# Ismailabi2.net
KiCad netlist of a schematic drawn in EAGLE
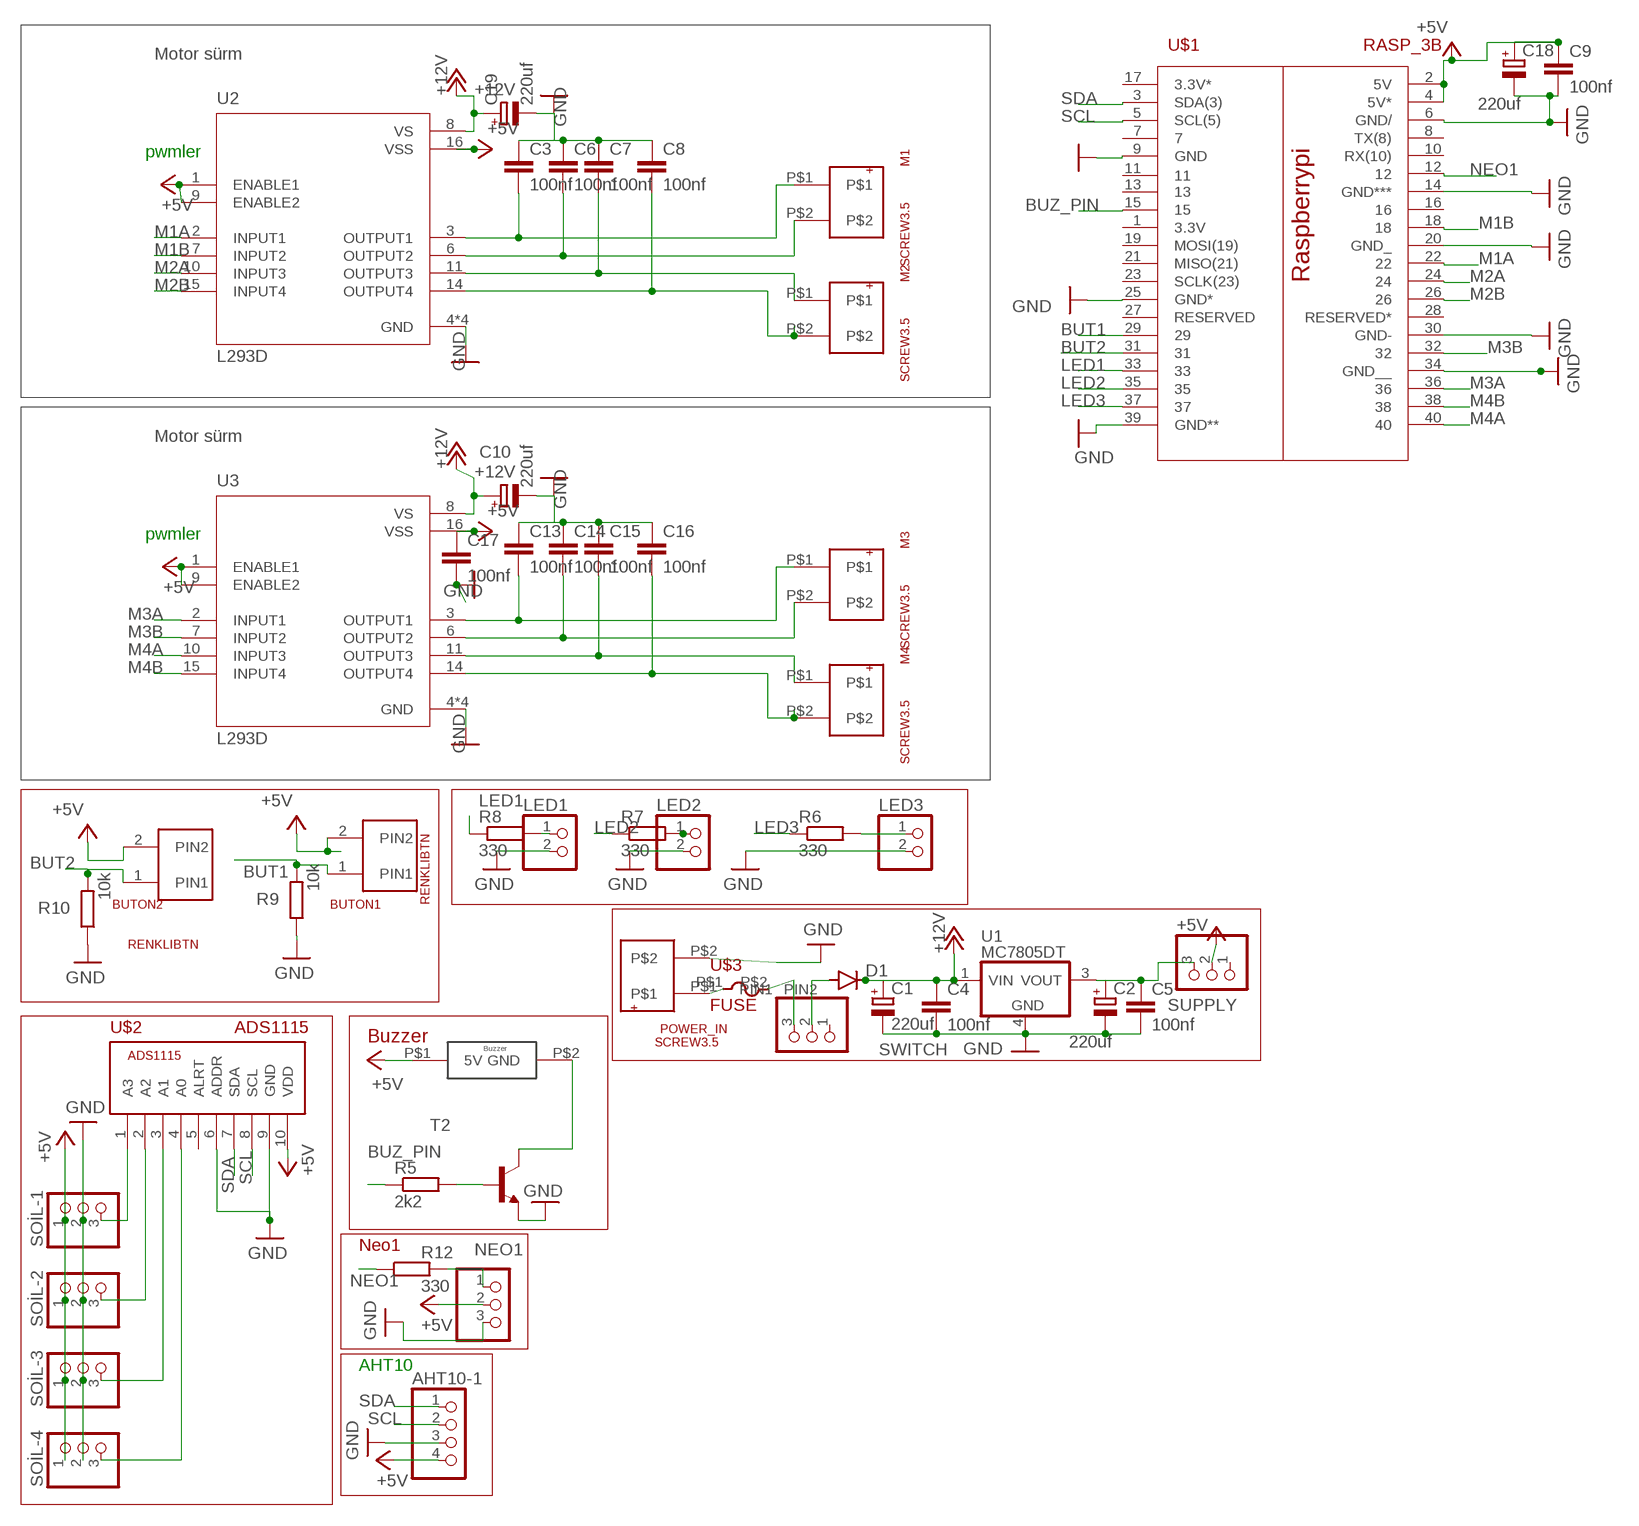
[diagram p0: schematic, sheet 1]

(export (version "E")
  (design (tool "Eeschema 10.0.6"))
  (components
    (comp (ref "AHT10-1")
      (value "PINHD-1X4")
      (footprint "eagle-import:1X04")
      (libsource (lib "eagle-import") (part "PINHD-1X4"))
    )
    (comp (ref "BUTON1")
      (value "RENKLIBTN")
      (footprint "eagle-import:BTN")
      (libsource (lib "eagle-import") (part "RENKLIBTN"))
    )
    (comp (ref "BUTON2")
      (value "RENKLIBTN")
      (footprint "eagle-import:BTN")
      (libsource (lib "eagle-import") (part "RENKLIBTN"))
    )
    (comp (ref "C1")
      (value "220uf")
      (footprint "eagle-import:153CLV-0605")
      (libsource (lib "eagle-import") (part "CPOL-EU153CLV-0605"))
    )
    (comp (ref "C2")
      (value "220uf")
      (footprint "eagle-import:153CLV-0605")
      (libsource (lib "eagle-import") (part "CPOL-EU153CLV-0605"))
    )
    (comp (ref "C3")
      (value "100nf")
      (footprint "eagle-import:C0603")
      (libsource (lib "eagle-import") (part "C-EUC0603"))
    )
    (comp (ref "C4")
      (value "100nf")
      (footprint "eagle-import:C0603")
      (libsource (lib "eagle-import") (part "C-EUC0603"))
    )
    (comp (ref "C5")
      (value "100nf")
      (footprint "eagle-import:C0603")
      (libsource (lib "eagle-import") (part "C-EUC0603"))
    )
    (comp (ref "C6")
      (value "100nf")
      (footprint "eagle-import:C0603")
      (libsource (lib "eagle-import") (part "C-EUC0603"))
    )
    (comp (ref "C7")
      (value "100nf")
      (footprint "eagle-import:C0603")
      (libsource (lib "eagle-import") (part "C-EUC0603"))
    )
    (comp (ref "C8")
      (value "100nf")
      (footprint "eagle-import:C0603")
      (libsource (lib "eagle-import") (part "C-EUC0603"))
    )
    (comp (ref "C9")
      (value "100nf")
      (footprint "eagle-import:C0603")
      (libsource (lib "eagle-import") (part "C-EUC0603"))
    )
    (comp (ref "C10")
      (value "220uf")
      (footprint "eagle-import:153CLV-0605")
      (libsource (lib "eagle-import") (part "CPOL-EU153CLV-0605"))
    )
    (comp (ref "C13")
      (value "100nf")
      (footprint "eagle-import:C0603")
      (libsource (lib "eagle-import") (part "C-EUC0603"))
    )
    (comp (ref "C14")
      (value "100nf")
      (footprint "eagle-import:C0603")
      (libsource (lib "eagle-import") (part "C-EUC0603"))
    )
    (comp (ref "C15")
      (value "100nf")
      (footprint "eagle-import:C0603")
      (libsource (lib "eagle-import") (part "C-EUC0603"))
    )
    (comp (ref "C16")
      (value "100nf")
      (footprint "eagle-import:C0603")
      (libsource (lib "eagle-import") (part "C-EUC0603"))
    )
    (comp (ref "C17")
      (value "100nf")
      (footprint "eagle-import:C0603")
      (libsource (lib "eagle-import") (part "C-EUC0603"))
    )
    (comp (ref "C18")
      (value "220uf")
      (footprint "eagle-import:153CLV-0605")
      (libsource (lib "eagle-import") (part "CPOL-EU153CLV-0605"))
    )
    (comp (ref "C19")
      (value "220uf")
      (footprint "eagle-import:153CLV-0605")
      (libsource (lib "eagle-import") (part "CPOL-EU153CLV-0605"))
    )
    (comp (ref "D1")
      (value "DIODE-DO-214AC")
      (footprint "eagle-import:DO-214AC")
      (libsource (lib "eagle-import") (part "DIODE-DO-214AC"))
    )
    (comp (ref "LED1")
      (value "PINHD-1X2")
      (footprint "eagle-import:1X02")
      (libsource (lib "eagle-import") (part "PINHD-1X2"))
    )
    (comp (ref "LED2")
      (value "PINHD-1X2")
      (footprint "eagle-import:1X02")
      (libsource (lib "eagle-import") (part "PINHD-1X2"))
    )
    (comp (ref "LED3")
      (value "PINHD-1X2")
      (footprint "eagle-import:1X02")
      (libsource (lib "eagle-import") (part "PINHD-1X2"))
    )
    (comp (ref "M1")
      (value "SCREW3.5")
      (footprint "eagle-import:CREWT")
      (libsource (lib "eagle-import") (part "SCREW3.5"))
    )
    (comp (ref "M2")
      (value "SCREW3.5")
      (footprint "eagle-import:CREWT")
      (libsource (lib "eagle-import") (part "SCREW3.5"))
    )
    (comp (ref "M3")
      (value "SCREW3.5")
      (footprint "eagle-import:CREWT")
      (libsource (lib "eagle-import") (part "SCREW3.5"))
    )
    (comp (ref "M4")
      (value "SCREW3.5")
      (footprint "eagle-import:CREWT")
      (libsource (lib "eagle-import") (part "SCREW3.5"))
    )
    (comp (ref "NEO1")
      (value "PINHD-1X3")
      (footprint "eagle-import:1X03")
      (libsource (lib "eagle-import") (part "PINHD-1X3"))
    )
    (comp (ref "POWER_IN")
      (value "SCREW3.5")
      (footprint "eagle-import:CREWT")
      (libsource (lib "eagle-import") (part "SCREW3.5"))
    )
    (comp (ref "R5")
      (value "2k2")
      (footprint "eagle-import:R0805")
      (libsource (lib "eagle-import") (part "R-EU_R0805"))
    )
    (comp (ref "R6")
      (value "330")
      (footprint "eagle-import:R0805")
      (libsource (lib "eagle-import") (part "R-EU_R0805"))
    )
    (comp (ref "R7")
      (value "330")
      (footprint "eagle-import:R0805")
      (libsource (lib "eagle-import") (part "R-EU_R0805"))
    )
    (comp (ref "R8")
      (value "330")
      (footprint "eagle-import:R0805")
      (libsource (lib "eagle-import") (part "R-EU_R0805"))
    )
    (comp (ref "R9")
      (value "10k")
      (footprint "eagle-import:R0805")
      (libsource (lib "eagle-import") (part "R-EU_R0805"))
    )
    (comp (ref "R10")
      (value "10k")
      (footprint "eagle-import:R0805")
      (libsource (lib "eagle-import") (part "R-EU_R0805"))
    )
    (comp (ref "R12")
      (value "330")
      (footprint "eagle-import:R0805")
      (libsource (lib "eagle-import") (part "R-EU_R0805"))
    )
    (comp (ref "SOİL-1")
      (value "PINHD-1X3")
      (footprint "eagle-import:1X03")
      (libsource (lib "eagle-import") (part "PINHD-1X3"))
    )
    (comp (ref "SOİL-2")
      (value "PINHD-1X3")
      (footprint "eagle-import:1X03")
      (libsource (lib "eagle-import") (part "PINHD-1X3"))
    )
    (comp (ref "SOİL-3")
      (value "PINHD-1X3")
      (footprint "eagle-import:1X03")
      (libsource (lib "eagle-import") (part "PINHD-1X3"))
    )
    (comp (ref "SOİL-4")
      (value "PINHD-1X3")
      (footprint "eagle-import:1X03")
      (libsource (lib "eagle-import") (part "PINHD-1X3"))
    )
    (comp (ref "SUPPLY")
      (value "PINHD-1X3")
      (footprint "eagle-import:1X03")
      (libsource (lib "eagle-import") (part "PINHD-1X3"))
    )
    (comp (ref "SWITCH")
      (value "PINHD-1X3")
      (footprint "eagle-import:1X03")
      (libsource (lib "eagle-import") (part "PINHD-1X3"))
    )
    (comp (ref "T2")
      (value "2N2222-NPN-TO92-EBC")
      (footprint "eagle-import:TO92-EBC")
      (libsource (lib "eagle-import") (part "-NPN-TO92-EBC2N2222"))
    )
    (comp (ref "U$1")
      (value "RASP_3B")
      (footprint "eagle-import:PI3B+")
      (libsource (lib "eagle-import") (part "RASP_3B"))
    )
    (comp (ref "U$2")
      (value "ADS1115")
      (footprint "eagle-import:ADS1115")
      (libsource (lib "eagle-import") (part "ADS1115"))
    )
    (comp (ref "U$3")
      (value "FUSE")
      (footprint "eagle-import:FUSE")
      (libsource (lib "eagle-import") (part "FUSE"))
    )
    (comp (ref "U$4")
      (value "BUZZER")
      (footprint "eagle-import:BUZZER")
      (libsource (lib "eagle-import") (part "BUZZER"))
    )
    (comp (ref "U1")
      (value "MC7805DT")
      (footprint "eagle-import:DPAK-3")
      (libsource (lib "eagle-import") (part "MC78DT05"))
    )
    (comp (ref "U2")
      (value "L293D")
      (footprint "eagle-import:DIP880W50P254L2000H510Q16")
      (fields (field (name "MF") "STMicroelectronics"))
      (libsource (lib "eagle-import") (part "L293D"))
    )
    (comp (ref "U3")
      (value "L293D")
      (footprint "eagle-import:DIP880W50P254L2000H510Q16")
      (fields (field (name "MF") "STMicroelectronics"))
      (libsource (lib "eagle-import") (part "L293D"))
    )
  )
  (nets
    (net (code "1") (name "+5V") (class "Default")
      (node (ref "AHT10-1") (pin "4") (pinfunction "4_4") (pintype "passive"))
      (node (ref "BUTON1") (pin "2") (pinfunction "PIN2_2") (pintype "bidirectional"))
      (node (ref "BUTON2") (pin "2") (pinfunction "PIN2_2") (pintype "bidirectional"))
      (node (ref "C17") (pin "1") (pinfunction "1_1") (pintype "passive"))
      (node (ref "C18") (pin "+") (pinfunction "+_+") (pintype "passive"))
      (node (ref "C9") (pin "1") (pinfunction "1_1") (pintype "passive"))
      (node (ref "NEO1") (pin "2") (pinfunction "2_2") (pintype "passive"))
      (node (ref "SOİL-1") (pin "1") (pinfunction "1_1") (pintype "passive"))
      (node (ref "SOİL-2") (pin "1") (pinfunction "1_1") (pintype "passive"))
      (node (ref "SOİL-3") (pin "1") (pinfunction "1_1") (pintype "passive"))
      (node (ref "SOİL-4") (pin "1") (pinfunction "1_1") (pintype "passive"))
      (node (ref "SUPPLY") (pin "2") (pinfunction "2_2") (pintype "passive"))
      (node (ref "U$1") (pin "2") (pinfunction "5V_2") (pintype "bidirectional"))
      (node (ref "U$1") (pin "4") (pinfunction "5V*_4") (pintype "bidirectional"))
      (node (ref "U$2") (pin "10") (pinfunction "VDD_10") (pintype "bidirectional"))
      (node (ref "U$4") (pin "P$1") (pinfunction "5V_P$1") (pintype "bidirectional"))
      (node (ref "U2") (pin "1") (pinfunction "ENABLE1_1") (pintype "input"))
      (node (ref "U2") (pin "16") (pinfunction "VSS_16") (pintype "power_in"))
      (node (ref "U2") (pin "9") (pinfunction "ENABLE2_9") (pintype "input"))
      (node (ref "U3") (pin "1") (pinfunction "ENABLE1_1") (pintype "input"))
      (node (ref "U3") (pin "16") (pinfunction "VSS_16") (pintype "power_in"))
      (node (ref "U3") (pin "9") (pinfunction "ENABLE2_9") (pintype "input"))
    )
    (net (code "2") (name "+12V") (class "Default")
      (node (ref "C1") (pin "+") (pinfunction "+_+") (pintype "passive"))
      (node (ref "C10") (pin "+") (pinfunction "+_+") (pintype "passive"))
      (node (ref "C19") (pin "+") (pinfunction "+_+") (pintype "passive"))
      (node (ref "C4") (pin "1") (pinfunction "1_1") (pintype "passive"))
      (node (ref "D1") (pin "C") (pinfunction "C_C") (pintype "passive"))
      (node (ref "U1") (pin "1") (pinfunction "VIN_1") (pintype "power_in"))
      (node (ref "U2") (pin "8") (pinfunction "VS_8") (pintype "power_in"))
      (node (ref "U3") (pin "8") (pinfunction "VS_8") (pintype "power_in"))
    )
    (net (code "3") (name "/BUT1") (class "Default")
      (node (ref "BUTON1") (pin "1") (pinfunction "PIN1_1") (pintype "bidirectional"))
      (node (ref "R9") (pin "2") (pinfunction "2_2") (pintype "passive"))
      (node (ref "U$1") (pin "29") (pinfunction "29_29") (pintype "bidirectional"))
    )
    (net (code "4") (name "/BUT2") (class "Default")
      (node (ref "BUTON2") (pin "1") (pinfunction "PIN1_1") (pintype "bidirectional"))
      (node (ref "R10") (pin "2") (pinfunction "2_2") (pintype "passive"))
      (node (ref "U$1") (pin "31") (pinfunction "31_31") (pintype "bidirectional"))
    )
    (net (code "5") (name "/BUZ_PIN") (class "Default")
      (node (ref "R5") (pin "1") (pinfunction "1_1") (pintype "passive"))
      (node (ref "U$1") (pin "15") (pinfunction "15_15") (pintype "bidirectional"))
    )
    (net (code "6") (name "/LED1") (class "Default")
      (node (ref "R8") (pin "1") (pinfunction "1_1") (pintype "passive"))
      (node (ref "U$1") (pin "33") (pinfunction "33_33") (pintype "bidirectional"))
    )
    (net (code "7") (name "/LED2") (class "Default")
      (node (ref "R7") (pin "1") (pinfunction "1_1") (pintype "passive"))
      (node (ref "U$1") (pin "35") (pinfunction "35_35") (pintype "bidirectional"))
    )
    (net (code "8") (name "/LED3") (class "Default")
      (node (ref "R6") (pin "1") (pinfunction "1_1") (pintype "passive"))
      (node (ref "U$1") (pin "37") (pinfunction "37_37") (pintype "bidirectional"))
    )
    (net (code "9") (name "/M1A") (class "Default")
      (node (ref "U$1") (pin "22") (pinfunction "22_22") (pintype "bidirectional"))
      (node (ref "U2") (pin "2") (pinfunction "INPUT1_2") (pintype "input"))
    )
    (net (code "10") (name "/M1B") (class "Default")
      (node (ref "U$1") (pin "18") (pinfunction "18_18") (pintype "bidirectional"))
      (node (ref "U2") (pin "7") (pinfunction "INPUT2_7") (pintype "input"))
    )
    (net (code "11") (name "/M2A") (class "Default")
      (node (ref "U$1") (pin "24") (pinfunction "24_24") (pintype "bidirectional"))
      (node (ref "U2") (pin "10") (pinfunction "INPUT3_10") (pintype "input"))
    )
    (net (code "12") (name "/M2B") (class "Default")
      (node (ref "U$1") (pin "26") (pinfunction "26_26") (pintype "bidirectional"))
      (node (ref "U2") (pin "15") (pinfunction "INPUT4_15") (pintype "input"))
    )
    (net (code "13") (name "/M3A") (class "Default")
      (node (ref "U$1") (pin "36") (pinfunction "36_36") (pintype "bidirectional"))
      (node (ref "U3") (pin "2") (pinfunction "INPUT1_2") (pintype "input"))
    )
    (net (code "14") (name "/M3B") (class "Default")
      (node (ref "U$1") (pin "32") (pinfunction "32_32") (pintype "bidirectional"))
      (node (ref "U3") (pin "7") (pinfunction "INPUT2_7") (pintype "input"))
    )
    (net (code "15") (name "/M4A") (class "Default")
      (node (ref "U$1") (pin "40") (pinfunction "40_40") (pintype "bidirectional"))
      (node (ref "U3") (pin "10") (pinfunction "INPUT3_10") (pintype "input"))
    )
    (net (code "16") (name "/M4B") (class "Default")
      (node (ref "U$1") (pin "38") (pinfunction "38_38") (pintype "bidirectional"))
      (node (ref "U3") (pin "15") (pinfunction "INPUT4_15") (pintype "input"))
    )
    (net (code "17") (name "/NEO1") (class "Default")
      (node (ref "R12") (pin "1") (pinfunction "1_1") (pintype "passive"))
      (node (ref "U$1") (pin "12") (pinfunction "12_12") (pintype "bidirectional"))
    )
    (net (code "18") (name "/SCL") (class "Default")
      (node (ref "AHT10-1") (pin "2") (pinfunction "2_2") (pintype "passive"))
      (node (ref "U$1") (pin "5") (pinfunction "SCL(5)_5") (pintype "bidirectional"))
      (node (ref "U$2") (pin "8") (pinfunction "SCL_8") (pintype "bidirectional"))
    )
    (net (code "19") (name "/SDA") (class "Default")
      (node (ref "AHT10-1") (pin "1") (pinfunction "1_1") (pintype "passive"))
      (node (ref "U$1") (pin "3") (pinfunction "SDA(3)_3") (pintype "bidirectional"))
      (node (ref "U$2") (pin "7") (pinfunction "SDA_7") (pintype "bidirectional"))
    )
    (net (code "20") (name "GND") (class "Default")
      (node (ref "AHT10-1") (pin "3") (pinfunction "3_3") (pintype "passive"))
      (node (ref "C1") (pin "-") (pinfunction "-_-") (pintype "passive"))
      (node (ref "C10") (pin "-") (pinfunction "-_-") (pintype "passive"))
      (node (ref "C13") (pin "1") (pinfunction "1_1") (pintype "passive"))
      (node (ref "C14") (pin "1") (pinfunction "1_1") (pintype "passive"))
      (node (ref "C15") (pin "1") (pinfunction "1_1") (pintype "passive"))
      (node (ref "C16") (pin "1") (pinfunction "1_1") (pintype "passive"))
      (node (ref "C17") (pin "2") (pinfunction "2_2") (pintype "passive"))
      (node (ref "C18") (pin "-") (pinfunction "-_-") (pintype "passive"))
      (node (ref "C19") (pin "-") (pinfunction "-_-") (pintype "passive"))
      (node (ref "C2") (pin "-") (pinfunction "-_-") (pintype "passive"))
      (node (ref "C3") (pin "1") (pinfunction "1_1") (pintype "passive"))
      (node (ref "C4") (pin "2") (pinfunction "2_2") (pintype "passive"))
      (node (ref "C5") (pin "2") (pinfunction "2_2") (pintype "passive"))
      (node (ref "C6") (pin "1") (pinfunction "1_1") (pintype "passive"))
      (node (ref "C7") (pin "1") (pinfunction "1_1") (pintype "passive"))
      (node (ref "C8") (pin "1") (pinfunction "1_1") (pintype "passive"))
      (node (ref "C9") (pin "2") (pinfunction "2_2") (pintype "passive"))
      (node (ref "LED1") (pin "2") (pinfunction "2_2") (pintype "passive"))
      (node (ref "LED2") (pin "2") (pinfunction "2_2") (pintype "passive"))
      (node (ref "LED3") (pin "2") (pinfunction "2_2") (pintype "passive"))
      (node (ref "NEO1") (pin "3") (pinfunction "3_3") (pintype "passive"))
      (node (ref "POWER_IN") (pin "P$2") (pinfunction "P$2_P$2") (pintype "bidirectional"))
      (node (ref "R10") (pin "1") (pinfunction "1_1") (pintype "passive"))
      (node (ref "R9") (pin "1") (pinfunction "1_1") (pintype "passive"))
      (node (ref "SOİL-1") (pin "2") (pinfunction "2_2") (pintype "passive"))
      (node (ref "SOİL-2") (pin "2") (pinfunction "2_2") (pintype "passive"))
      (node (ref "SOİL-3") (pin "2") (pinfunction "2_2") (pintype "passive"))
      (node (ref "SOİL-4") (pin "2") (pinfunction "2_2") (pintype "passive"))
      (node (ref "T2") (pin "E") (pinfunction "E_E") (pintype "passive"))
      (node (ref "U$1") (pin "14") (pinfunction "GND***_14") (pintype "bidirectional"))
      (node (ref "U$1") (pin "20") (pinfunction "GND__20") (pintype "bidirectional"))
      (node (ref "U$1") (pin "25") (pinfunction "GND*_25") (pintype "bidirectional"))
      (node (ref "U$1") (pin "30") (pinfunction "GND-_30") (pintype "bidirectional"))
      (node (ref "U$1") (pin "34") (pinfunction "GND___34") (pintype "bidirectional"))
      (node (ref "U$1") (pin "39") (pinfunction "GND**_39") (pintype "bidirectional"))
      (node (ref "U$1") (pin "6") (pinfunction "GND/_6") (pintype "bidirectional"))
      (node (ref "U$1") (pin "9") (pinfunction "GND_9") (pintype "bidirectional"))
      (node (ref "U$2") (pin "6") (pinfunction "ADDR_6") (pintype "bidirectional"))
      (node (ref "U$2") (pin "9") (pinfunction "GND_9") (pintype "bidirectional"))
      (node (ref "U1") (pin "4") (pinfunction "GND_4") (pintype "power_in"))
      (node (ref "U2") (pin "12") (pinfunction "GND_12") (pintype "power_in"))
      (node (ref "U2") (pin "13") (pinfunction "GND_13") (pintype "power_in"))
      (node (ref "U2") (pin "4") (pinfunction "GND_4") (pintype "power_in"))
      (node (ref "U2") (pin "5") (pinfunction "GND_5") (pintype "power_in"))
      (node (ref "U3") (pin "12") (pinfunction "GND_12") (pintype "power_in"))
      (node (ref "U3") (pin "13") (pinfunction "GND_13") (pintype "power_in"))
      (node (ref "U3") (pin "4") (pinfunction "GND_4") (pintype "power_in"))
      (node (ref "U3") (pin "5") (pinfunction "GND_5") (pintype "power_in"))
    )
    (net (code "21") (name "Net-(D1-PadA)") (class "Default")
      (node (ref "D1") (pin "A") (pinfunction "A_A") (pintype "passive"))
      (node (ref "SWITCH") (pin "2") (pinfunction "2_2") (pintype "passive"))
    )
    (net (code "22") (name "Net-(LED1-Pad1)") (class "Default")
      (node (ref "LED1") (pin "1") (pinfunction "1_1") (pintype "passive"))
      (node (ref "R8") (pin "2") (pinfunction "2_2") (pintype "passive"))
    )
    (net (code "23") (name "Net-(LED2-Pad1)") (class "Default")
      (node (ref "LED2") (pin "1") (pinfunction "1_1") (pintype "passive"))
      (node (ref "R7") (pin "2") (pinfunction "2_2") (pintype "passive"))
    )
    (net (code "24") (name "Net-(LED3-Pad1)") (class "Default")
      (node (ref "LED3") (pin "1") (pinfunction "1_1") (pintype "passive"))
      (node (ref "R6") (pin "2") (pinfunction "2_2") (pintype "passive"))
    )
    (net (code "25") (name "Net-(NEO1-Pad1)") (class "Default")
      (node (ref "NEO1") (pin "1") (pinfunction "1_1") (pintype "passive"))
      (node (ref "R12") (pin "2") (pinfunction "2_2") (pintype "passive"))
    )
    (net (code "26") (name "Net-(R5-Pad2)") (class "Default")
      (node (ref "R5") (pin "2") (pinfunction "2_2") (pintype "passive"))
      (node (ref "T2") (pin "B") (pinfunction "B_B") (pintype "passive"))
    )
    (net (code "27") (name "Net-(U$2-A0)") (class "Default")
      (node (ref "SOİL-4") (pin "3") (pinfunction "3_3") (pintype "passive"))
      (node (ref "U$2") (pin "4") (pinfunction "A0_4") (pintype "bidirectional"))
    )
    (net (code "28") (name "Net-(U$2-A1)") (class "Default")
      (node (ref "SOİL-3") (pin "3") (pinfunction "3_3") (pintype "passive"))
      (node (ref "U$2") (pin "3") (pinfunction "A1_3") (pintype "bidirectional"))
    )
    (net (code "29") (name "Net-(U$2-A2)") (class "Default")
      (node (ref "SOİL-2") (pin "3") (pinfunction "3_3") (pintype "passive"))
      (node (ref "U$2") (pin "2") (pinfunction "A2_2") (pintype "bidirectional"))
    )
    (net (code "30") (name "Net-(U$2-A3)") (class "Default")
      (node (ref "SOİL-1") (pin "3") (pinfunction "3_3") (pintype "passive"))
      (node (ref "U$2") (pin "1") (pinfunction "A3_1") (pintype "bidirectional"))
    )
    (net (code "31") (name "Net-(U$3-PIN1)") (class "Default")
      (node (ref "POWER_IN") (pin "P$1") (pinfunction "P$1_P$1") (pintype "bidirectional"))
      (node (ref "U$3") (pin "P$1") (pinfunction "PIN1_P$1") (pintype "bidirectional"))
    )
    (net (code "32") (name "Net-(U$3-PIN2)") (class "Default")
      (node (ref "SWITCH") (pin "3") (pinfunction "3_3") (pintype "passive"))
      (node (ref "U$3") (pin "P$2") (pinfunction "PIN2_P$2") (pintype "bidirectional"))
    )
    (net (code "33") (name "Net-(U$4-GND)") (class "Default")
      (node (ref "T2") (pin "C") (pinfunction "C_C") (pintype "passive"))
      (node (ref "U$4") (pin "P$2") (pinfunction "GND_P$2") (pintype "bidirectional"))
    )
    (net (code "34") (name "Net-(U1-VOUT)") (class "Default")
      (node (ref "C2") (pin "+") (pinfunction "+_+") (pintype "passive"))
      (node (ref "C5") (pin "1") (pinfunction "1_1") (pintype "passive"))
      (node (ref "SUPPLY") (pin "3") (pinfunction "3_3") (pintype "passive"))
      (node (ref "U1") (pin "3") (pinfunction "VOUT_3") (pintype "power_in"))
    )
    (net (code "35") (name "Net-(U2-OUTPUT1)") (class "Default")
      (node (ref "C3") (pin "2") (pinfunction "2_2") (pintype "passive"))
      (node (ref "M1") (pin "P$1") (pinfunction "P$1_P$1") (pintype "bidirectional"))
      (node (ref "U2") (pin "3") (pinfunction "OUTPUT1_3") (pintype "output"))
    )
    (net (code "36") (name "Net-(U2-OUTPUT2)") (class "Default")
      (node (ref "C6") (pin "2") (pinfunction "2_2") (pintype "passive"))
      (node (ref "M1") (pin "P$2") (pinfunction "P$2_P$2") (pintype "bidirectional"))
      (node (ref "U2") (pin "6") (pinfunction "OUTPUT2_6") (pintype "output"))
    )
    (net (code "37") (name "Net-(U2-OUTPUT3)") (class "Default")
      (node (ref "C7") (pin "2") (pinfunction "2_2") (pintype "passive"))
      (node (ref "M2") (pin "P$1") (pinfunction "P$1_P$1") (pintype "bidirectional"))
      (node (ref "U2") (pin "11") (pinfunction "OUTPUT3_11") (pintype "output"))
    )
    (net (code "38") (name "Net-(U2-OUTPUT4)") (class "Default")
      (node (ref "C8") (pin "2") (pinfunction "2_2") (pintype "passive"))
      (node (ref "M2") (pin "P$2") (pinfunction "P$2_P$2") (pintype "bidirectional"))
      (node (ref "U2") (pin "14") (pinfunction "OUTPUT4_14") (pintype "output"))
    )
    (net (code "39") (name "Net-(U3-OUTPUT1)") (class "Default")
      (node (ref "C13") (pin "2") (pinfunction "2_2") (pintype "passive"))
      (node (ref "M3") (pin "P$1") (pinfunction "P$1_P$1") (pintype "bidirectional"))
      (node (ref "U3") (pin "3") (pinfunction "OUTPUT1_3") (pintype "output"))
    )
    (net (code "40") (name "Net-(U3-OUTPUT2)") (class "Default")
      (node (ref "C14") (pin "2") (pinfunction "2_2") (pintype "passive"))
      (node (ref "M3") (pin "P$2") (pinfunction "P$2_P$2") (pintype "bidirectional"))
      (node (ref "U3") (pin "6") (pinfunction "OUTPUT2_6") (pintype "output"))
    )
    (net (code "41") (name "Net-(U3-OUTPUT3)") (class "Default")
      (node (ref "C15") (pin "2") (pinfunction "2_2") (pintype "passive"))
      (node (ref "M4") (pin "P$1") (pinfunction "P$1_P$1") (pintype "bidirectional"))
      (node (ref "U3") (pin "11") (pinfunction "OUTPUT3_11") (pintype "output"))
    )
    (net (code "42") (name "Net-(U3-OUTPUT4)") (class "Default")
      (node (ref "C16") (pin "2") (pinfunction "2_2") (pintype "passive"))
      (node (ref "M4") (pin "P$2") (pinfunction "P$2_P$2") (pintype "bidirectional"))
      (node (ref "U3") (pin "14") (pinfunction "OUTPUT4_14") (pintype "output"))
    )
    (net (code "43") (name "unconnected-(SUPPLY-Pad1)") (class "Default")
      (node (ref "SUPPLY") (pin "1") (pinfunction "1_1") (pintype "passive"))
    )
    (net (code "44") (name "unconnected-(SWITCH-Pad1)") (class "Default")
      (node (ref "SWITCH") (pin "1") (pinfunction "1_1") (pintype "passive"))
    )
    (net (code "45") (name "unconnected-(U$1-3.3V*-Pad17)") (class "Default")
      (node (ref "U$1") (pin "17") (pinfunction "3.3V*_17") (pintype "bidirectional"))
    )
    (net (code "46") (name "unconnected-(U$1-3.3V-Pad1)") (class "Default")
      (node (ref "U$1") (pin "1") (pinfunction "3.3V_1") (pintype "bidirectional"))
    )
    (net (code "47") (name "unconnected-(U$1-MISO(21)-Pad21)") (class "Default")
      (node (ref "U$1") (pin "21") (pinfunction "MISO(21)_21") (pintype "bidirectional"))
    )
    (net (code "48") (name "unconnected-(U$1-MOSI(19)-Pad19)") (class "Default")
      (node (ref "U$1") (pin "19") (pinfunction "MOSI(19)_19") (pintype "bidirectional"))
    )
    (net (code "49") (name "unconnected-(U$1-Pad7)") (class "Default")
      (node (ref "U$1") (pin "7") (pinfunction "7_7") (pintype "bidirectional"))
    )
    (net (code "50") (name "unconnected-(U$1-Pad11)") (class "Default")
      (node (ref "U$1") (pin "11") (pinfunction "11_11") (pintype "bidirectional"))
    )
    (net (code "51") (name "unconnected-(U$1-Pad13)") (class "Default")
      (node (ref "U$1") (pin "13") (pinfunction "13_13") (pintype "bidirectional"))
    )
    (net (code "52") (name "unconnected-(U$1-Pad16)") (class "Default")
      (node (ref "U$1") (pin "16") (pinfunction "16_16") (pintype "bidirectional"))
    )
    (net (code "53") (name "unconnected-(U$1-RESERVED*-Pad28)") (class "Default")
      (node (ref "U$1") (pin "28") (pinfunction "RESERVED*_28") (pintype "bidirectional"))
    )
    (net (code "54") (name "unconnected-(U$1-RESERVED-Pad27)") (class "Default")
      (node (ref "U$1") (pin "27") (pinfunction "RESERVED_27") (pintype "bidirectional"))
    )
    (net (code "55") (name "unconnected-(U$1-RX(10)-Pad10)") (class "Default")
      (node (ref "U$1") (pin "10") (pinfunction "RX(10)_10") (pintype "bidirectional"))
    )
    (net (code "56") (name "unconnected-(U$1-SCLK(23)-Pad23)") (class "Default")
      (node (ref "U$1") (pin "23") (pinfunction "SCLK(23)_23") (pintype "bidirectional"))
    )
    (net (code "57") (name "unconnected-(U$1-TX(8)-Pad8)") (class "Default")
      (node (ref "U$1") (pin "8") (pinfunction "TX(8)_8") (pintype "bidirectional"))
    )
    (net (code "58") (name "unconnected-(U$2-ALRT-Pad5)") (class "Default")
      (node (ref "U$2") (pin "5") (pinfunction "ALRT_5") (pintype "bidirectional"))
    )
  )
)
